# SD_card.net
KiCad netlist of a schematic drawn in Altium Designer
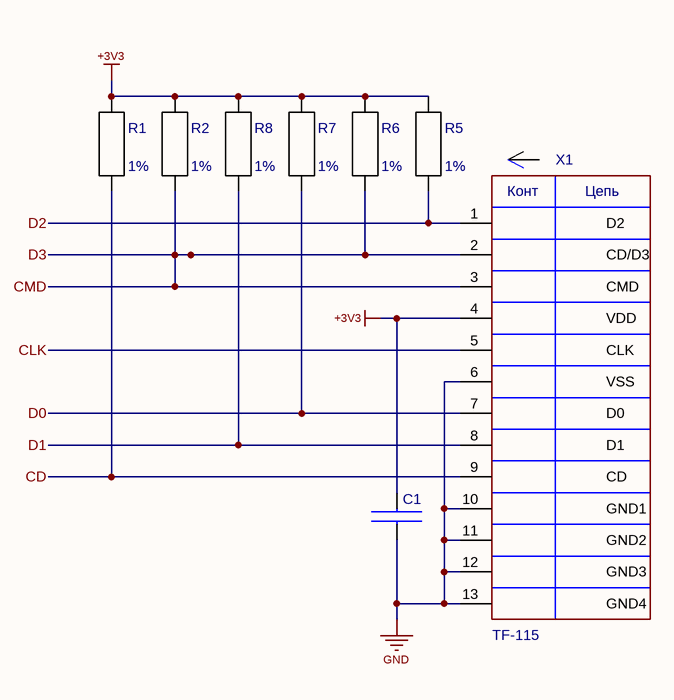
[diagram p0: SD_card.SchDoc]

(export (version "E")
  (design (tool "Eeschema 10.0.6"))
  (components
    (comp (ref "C1")
      (value "0402-0.1uF-50V-10%-X7R")
      (fields (field (name "TOLERANCE") "10%"))
      (libsource (lib "") (part "root_1__*_1"))
    )
    (comp (ref "R1")
      (value "0402-10k-1%-1/16 W-100ppm")
      (fields (field (name "TOLERANCE") "1%"))
      (libsource (lib "altium-import") (part "root_1__*"))
    )
    (comp (ref "R2")
      (value "0402-10k-1%-1/16 W-100ppm")
      (fields (field (name "TOLERANCE") "1%"))
      (libsource (lib "altium-import") (part "root_1__*"))
    )
    (comp (ref "R5")
      (value "0402-100k-1%-1/16 W-100ppm")
      (fields (field (name "TOLERANCE") "1%"))
      (libsource (lib "altium-import") (part "root_1__*"))
    )
    (comp (ref "R6")
      (value "0402-100k-1%-1/16 W-100ppm")
      (fields (field (name "TOLERANCE") "1%"))
      (libsource (lib "altium-import") (part "root_1__*"))
    )
    (comp (ref "R7")
      (value "0402-100k-1%-1/16 W-100ppm")
      (fields (field (name "TOLERANCE") "1%"))
      (libsource (lib "altium-import") (part "root_1__*"))
    )
    (comp (ref "R8")
      (value "0402-100k-1%-1/16 W-100ppm")
      (fields (field (name "TOLERANCE") "1%"))
      (libsource (lib "altium-import") (part "root_1__*"))
    )
    (comp (ref "X1") (value "TF-115") (libsource (lib "altium-import") (part "root_0__*")))
  )
  (nets
    (net (code "1") (name "+3V3") (class "Default")
      (node (ref "C1") (pin "2") (pinfunction "2_2") (pintype "passive"))
      (node (ref "R1") (pin "2") (pinfunction "2_2") (pintype "passive"))
      (node (ref "R2") (pin "2") (pinfunction "2_2") (pintype "passive"))
      (node (ref "R5") (pin "2") (pinfunction "2_2") (pintype "passive"))
      (node (ref "R6") (pin "2") (pinfunction "2_2") (pintype "passive"))
      (node (ref "R7") (pin "2") (pinfunction "2_2") (pintype "passive"))
      (node (ref "R8") (pin "2") (pinfunction "2_2") (pintype "passive"))
      (node (ref "X1") (pin "4") (pinfunction "VDD_4") (pintype "passive"))
    )
    (net (code "2") (name "/CD") (class "Default")
      (node (ref "R1") (pin "1") (pinfunction "1_1") (pintype "passive"))
      (node (ref "X1") (pin "9") (pinfunction "CD_9") (pintype "passive"))
    )
    (net (code "3") (name "/CLK") (class "Default")
      (node (ref "X1") (pin "5") (pinfunction "CLK_5") (pintype "passive"))
    )
    (net (code "4") (name "/CMD") (class "Default")
      (node (ref "R2") (pin "1") (pinfunction "1_1") (pintype "passive"))
      (node (ref "R6") (pin "1") (pinfunction "1_1") (pintype "passive"))
      (node (ref "X1") (pin "2") (pinfunction "CD/D3_2") (pintype "passive"))
      (node (ref "X1") (pin "3") (pinfunction "CMD_3") (pintype "passive"))
    )
    (net (code "5") (name "/D0") (class "Default")
      (node (ref "R7") (pin "1") (pinfunction "1_1") (pintype "passive"))
      (node (ref "X1") (pin "7") (pinfunction "D0_7") (pintype "passive"))
    )
    (net (code "6") (name "/D1") (class "Default")
      (node (ref "R8") (pin "1") (pinfunction "1_1") (pintype "passive"))
      (node (ref "X1") (pin "8") (pinfunction "D1_8") (pintype "passive"))
    )
    (net (code "7") (name "/D2") (class "Default")
      (node (ref "R5") (pin "1") (pinfunction "1_1") (pintype "passive"))
      (node (ref "X1") (pin "1") (pinfunction "D2_1") (pintype "passive"))
    )
    (net (code "8") (name "GND") (class "Default")
      (node (ref "C1") (pin "1") (pinfunction "1_1") (pintype "passive"))
      (node (ref "X1") (pin "10") (pinfunction "GND1_10") (pintype "power_in"))
      (node (ref "X1") (pin "11") (pinfunction "GND2_11") (pintype "power_in"))
      (node (ref "X1") (pin "12") (pinfunction "GND3_12") (pintype "power_in"))
      (node (ref "X1") (pin "13") (pinfunction "GND4_13") (pintype "power_in"))
      (node (ref "X1") (pin "6") (pinfunction "VSS_6") (pintype "power_in"))
    )
  )
)
